# Telemetry_868Mhz.net
KiCad netlist of a schematic drawn in Altium Designer
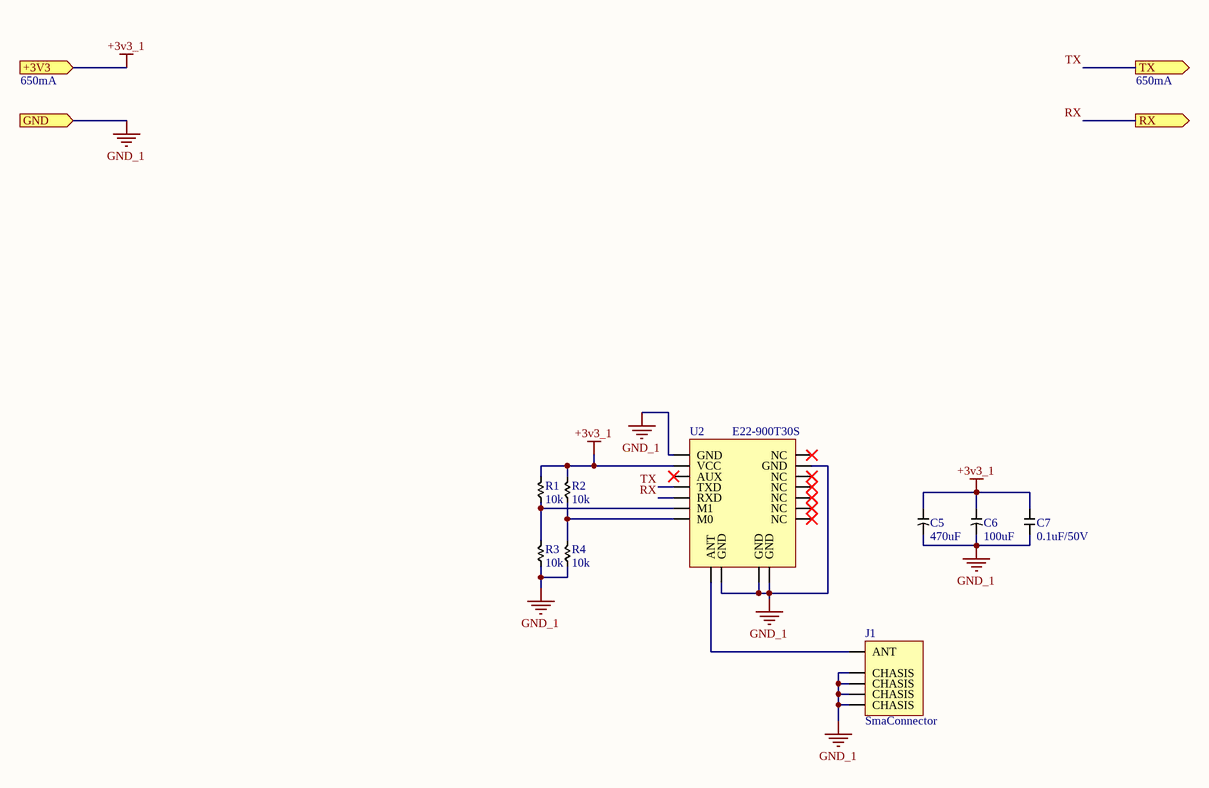
[diagram p0: Telemetry_868Mhz.SchDoc]

(export (version "E")
  (design (tool "Eeschema 10.0.6"))
  (components
    (comp (ref "C5")
      (value "470uF")
      (footprint "BXJ25VC470MJ10TP")
      (description "CAP.EL.470uF 25V 10x10 105C 5000Hrs SMD")
      (libsource (lib "Roket_Library") (part "BXJ25VC470MJ10TP"))
    )
    (comp (ref "C6")
      (value "100uF")
      (footprint "BXJ25VC470MJ10TP")
      (description "CAP.EL.100uF 50V 10x10 105C SMD SAMWHA")
      (libsource (lib "Roket_Library") (part "CK1H107M10010VR"))
    )
    (comp (ref "C7")
      (value "0.1uF/50V")
      (footprint "Cap_0805")
      (description "MLCC (2012) 0805 100nF 50VDC ±5% X7R")
      (libsource (lib "Roket_Library") (part "CL21B104JBCNNNC"))
    )
    (comp (ref "J1")
      (value "SmaConnector")
      (footprint "RightAngled_SMA_Connector")
      (description "RP-SMA Connector Receptacle, Male Pin 50Ohm Through Hole, Right Angle Solder")
      (libsource (lib "Roket_Library") (part "L-KLS1-SMA002-B"))
    )
    (comp (ref "R1")
      (value "10k")
      (footprint "RES_0805")
      (description "RES.(2012) 0805 10K Ohms 5% 1/8W-S 100PPM")
      (libsource (lib "Roket_Library") (part "0805S8J0103T5E"))
    )
    (comp (ref "R2")
      (value "10k")
      (footprint "RES_0805")
      (description "RES.(2012) 0805 10K Ohms 5% 1/8W-S 100PPM")
      (libsource (lib "Roket_Library") (part "0805S8J0103T5E"))
    )
    (comp (ref "R3")
      (value "10k")
      (footprint "RES_0805")
      (description "RES.(2012) 0805 10K Ohms 5% 1/8W-S 100PPM")
      (libsource (lib "Roket_Library") (part "0805S8J0103T5E"))
    )
    (comp (ref "R4")
      (value "10k")
      (footprint "RES_0805")
      (description "RES.(2012) 0805 10K Ohms 5% 1/8W-S 100PPM")
      (libsource (lib "Roket_Library") (part "0805S8J0103T5E"))
    )
    (comp (ref "U2")
      (value "E22-900T30S")
      (footprint "E22-900T30S")
      (libsource (lib "Roket_Library") (part "E22-900T30S"))
    )
  )
  (nets
    (net (code "1") (name "+3v3_1") (class "Default")
      (node (ref "C5") (pin "1") (pinfunction "1_1") (pintype "passive"))
      (node (ref "C6") (pin "1") (pinfunction "1_1") (pintype "passive"))
      (node (ref "C7") (pin "1") (pinfunction "1_1") (pintype "passive"))
      (node (ref "R1") (pin "2") (pinfunction "2_2") (pintype "passive"))
      (node (ref "R2") (pin "2") (pinfunction "2_2") (pintype "passive"))
      (node (ref "U2") (pin "6") (pinfunction "VCC_6") (pintype "passive"))
    )
    (net (code "2") (name "/RX") (class "Default")
      (node (ref "U2") (pin "3") (pinfunction "RXD_3") (pintype "passive"))
    )
    (net (code "3") (name "/TX") (class "Default")
      (node (ref "U2") (pin "4") (pinfunction "TXD_4") (pintype "passive"))
    )
    (net (code "4") (name "GND_1") (class "Default")
      (node (ref "C5") (pin "2") (pinfunction "2_2") (pintype "passive"))
      (node (ref "C6") (pin "2") (pinfunction "2_2") (pintype "passive"))
      (node (ref "C7") (pin "2") (pinfunction "2_2") (pintype "passive"))
      (node (ref "J1") (pin "2") (pinfunction "CHASIS_2") (pintype "passive"))
      (node (ref "J1") (pin "3") (pinfunction "CHASIS_3") (pintype "passive"))
      (node (ref "J1") (pin "4") (pinfunction "CHASIS_4") (pintype "passive"))
      (node (ref "J1") (pin "5") (pinfunction "CHASIS_5") (pintype "passive"))
      (node (ref "R3") (pin "1") (pinfunction "1_1") (pintype "passive"))
      (node (ref "R4") (pin "1") (pinfunction "1_1") (pintype "passive"))
      (node (ref "U2") (pin "15") (pinfunction "GND_15") (pintype "passive"))
      (node (ref "U2") (pin "16") (pinfunction "GND_16") (pintype "passive"))
      (node (ref "U2") (pin "17") (pinfunction "GND_17") (pintype "passive"))
      (node (ref "U2") (pin "7") (pinfunction "GND_7") (pintype "passive"))
      (node (ref "U2") (pin "9") (pinfunction "GND_9") (pintype "passive"))
    )
    (net (code "5") (name "Net-(J1-ANT)") (class "Default")
      (node (ref "J1") (pin "1") (pinfunction "ANT_1") (pintype "passive"))
      (node (ref "U2") (pin "18") (pinfunction "ANT_18") (pintype "passive"))
    )
    (net (code "6") (name "Net-(U2-M0)") (class "Default")
      (node (ref "R2") (pin "1") (pinfunction "1_1") (pintype "passive"))
      (node (ref "R4") (pin "2") (pinfunction "2_2") (pintype "passive"))
      (node (ref "U2") (pin "1") (pinfunction "M0_1") (pintype "passive"))
    )
    (net (code "7") (name "Net-(U2-M1)") (class "Default")
      (node (ref "R1") (pin "1") (pinfunction "1_1") (pintype "passive"))
      (node (ref "R3") (pin "2") (pinfunction "2_2") (pintype "passive"))
      (node (ref "U2") (pin "2") (pinfunction "M1_2") (pintype "passive"))
    )
    (net (code "8") (name "unconnected-(U2-AUX-Pad5)") (class "Default")
      (node (ref "U2") (pin "5") (pinfunction "AUX_5") (pintype "passive+no_connect"))
    )
    (net (code "9") (name "unconnected-(U2-NC-Pad8)") (class "Default")
      (node (ref "U2") (pin "8") (pinfunction "NC_8") (pintype "passive+no_connect"))
    )
    (net (code "10") (name "unconnected-(U2-NC-Pad10)") (class "Default")
      (node (ref "U2") (pin "10") (pinfunction "NC_10") (pintype "passive+no_connect"))
    )
    (net (code "11") (name "unconnected-(U2-NC-Pad11)") (class "Default")
      (node (ref "U2") (pin "11") (pinfunction "NC_11") (pintype "passive+no_connect"))
    )
    (net (code "12") (name "unconnected-(U2-NC-Pad12)") (class "Default")
      (node (ref "U2") (pin "12") (pinfunction "NC_12") (pintype "passive+no_connect"))
    )
    (net (code "13") (name "unconnected-(U2-NC-Pad13)") (class "Default")
      (node (ref "U2") (pin "13") (pinfunction "NC_13") (pintype "passive+no_connect"))
    )
    (net (code "14") (name "unconnected-(U2-NC-Pad14)") (class "Default")
      (node (ref "U2") (pin "14") (pinfunction "NC_14") (pintype "passive+no_connect"))
    )
  )
)
